# design.net
KiCad netlist of a schematic drawn in Altium Designer
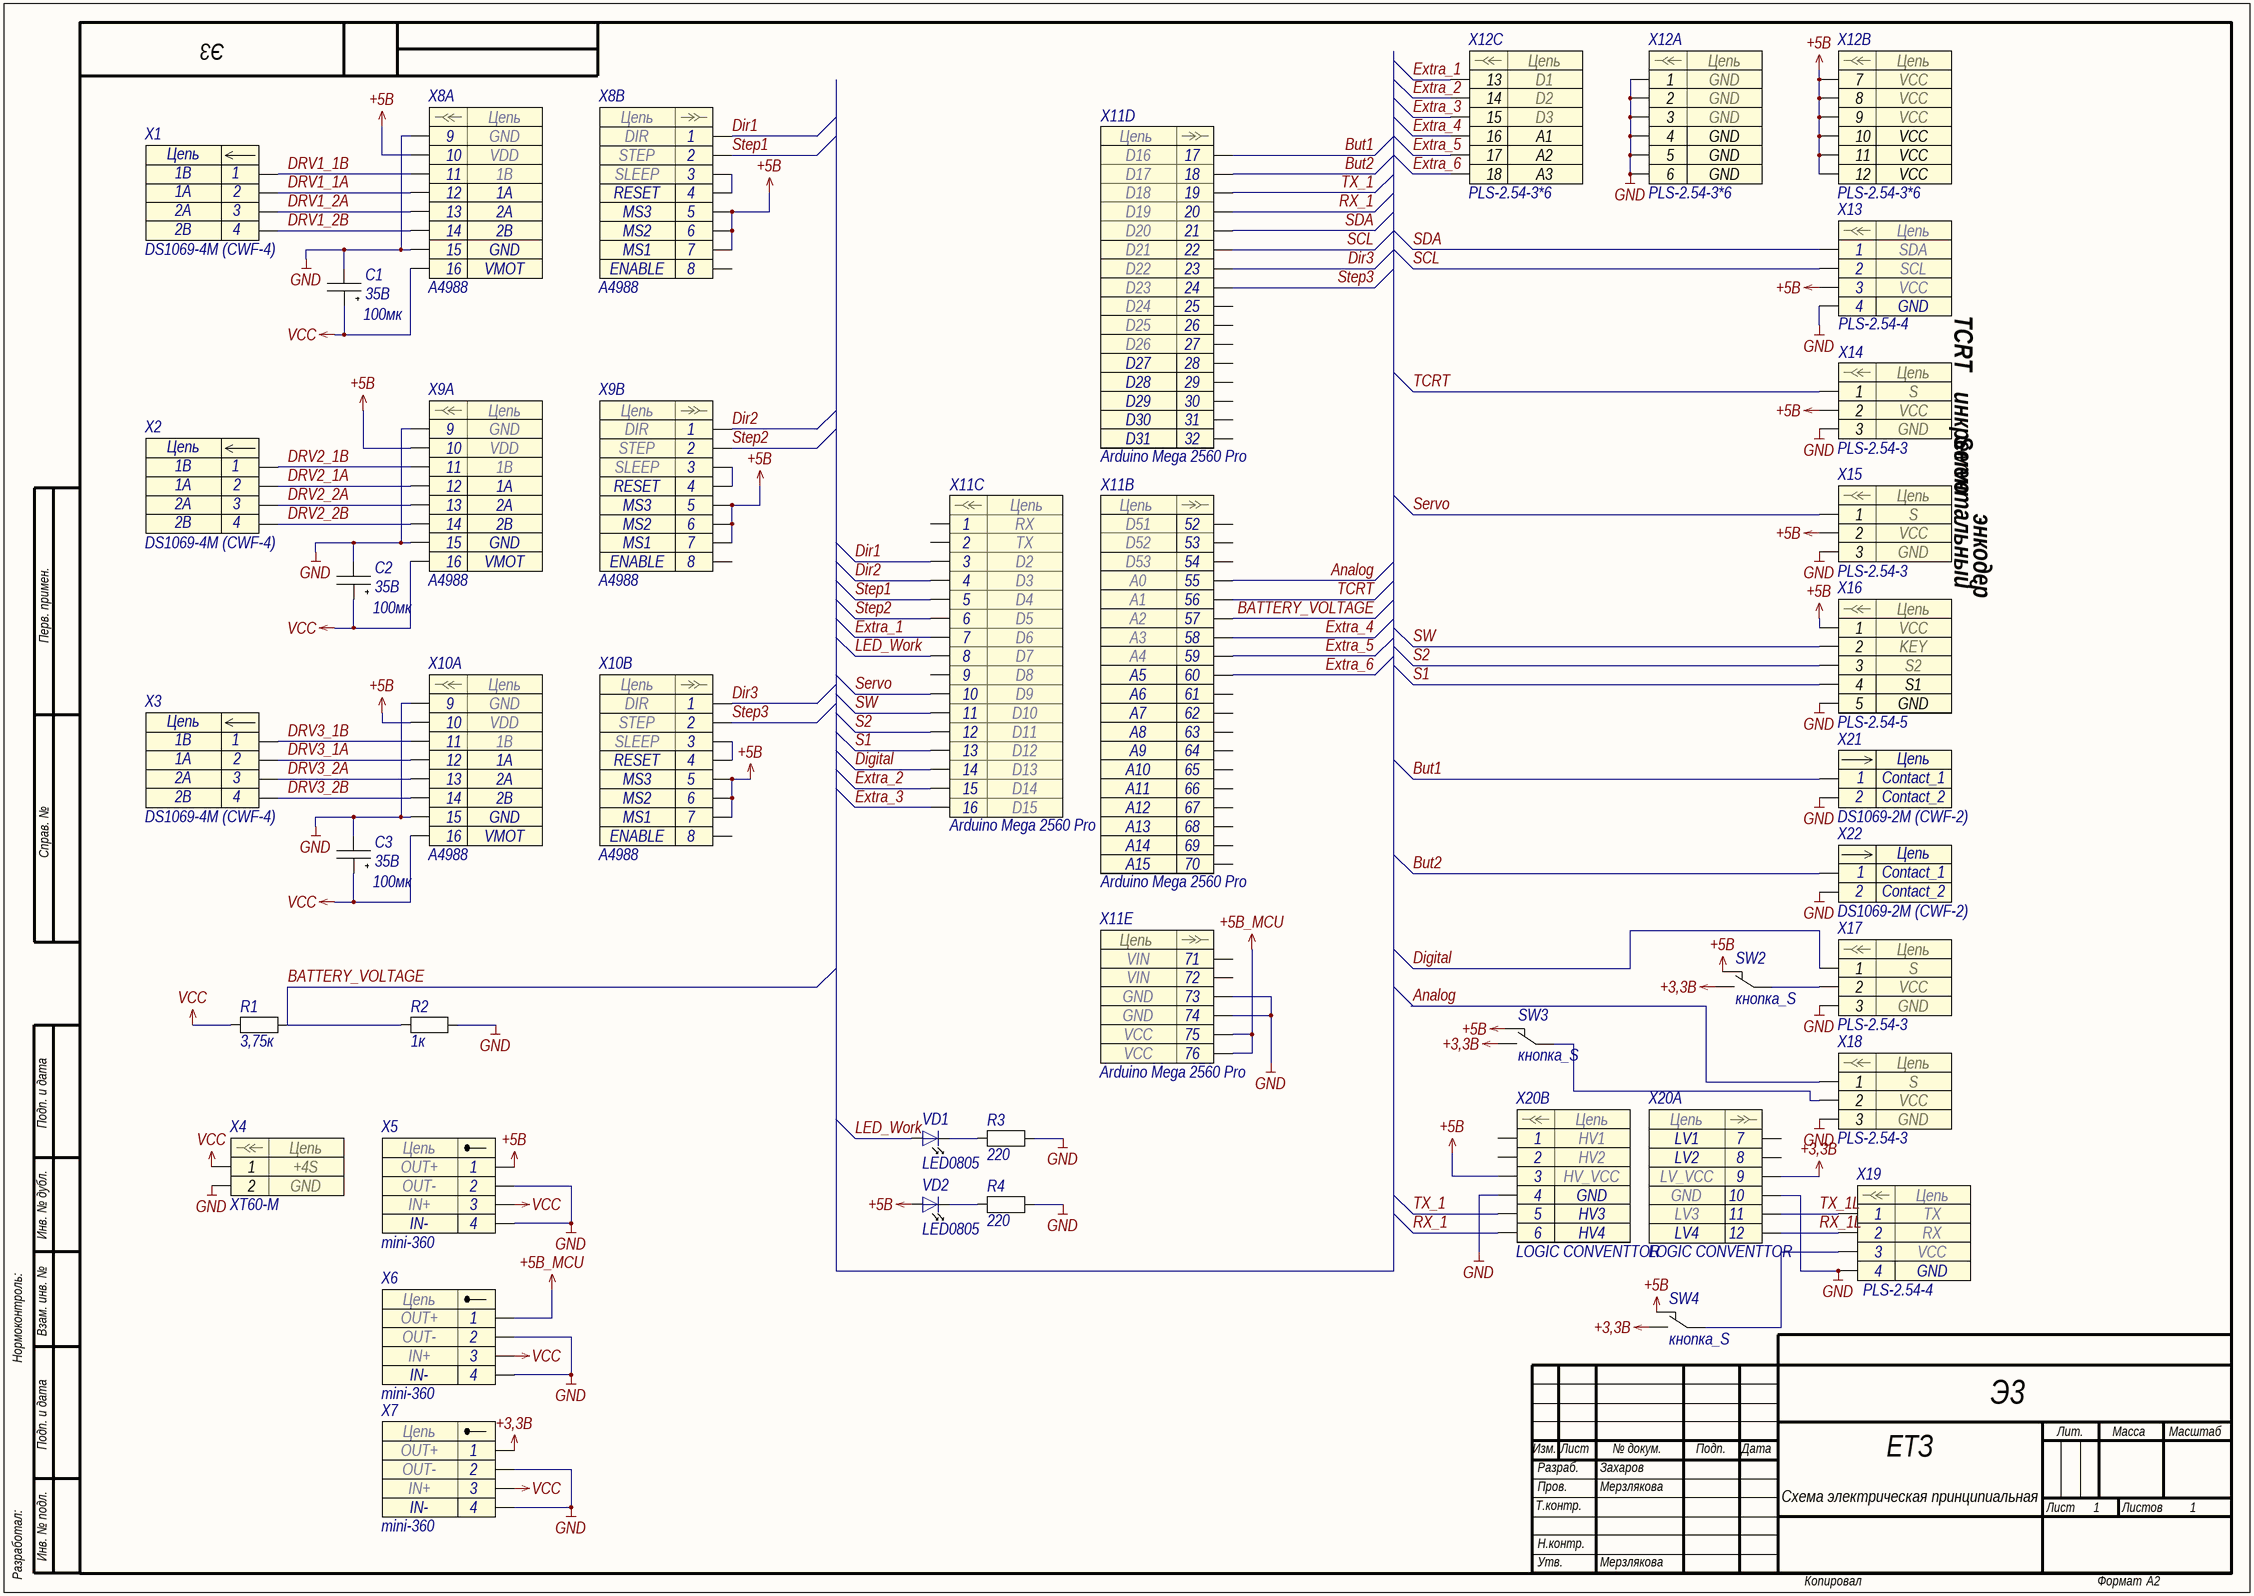
[diagram p0: Проект_ЕТЗ.SchDoc]

(export (version "E")
  (design (tool "Eeschema 10.0.6"))
  (components
    (comp (ref "C1")
      (value "am")
      (footprint "SK050M0100B3F-0811-up")
      (fields (field (name "VOLTAGE") "35В") (field (name "NOMINAL") "100мк"))
      (libsource (lib "LibraryPloshchadnaia") (part "CAPATION+470мк35В"))
    )
    (comp (ref "C2")
      (value "am")
      (footprint "SK050M0100B3F-0811-up")
      (fields (field (name "VOLTAGE") "35В") (field (name "NOMINAL") "100мк"))
      (libsource (lib "LibraryPloshchadnaia") (part "CAPATION+470мк35В"))
    )
    (comp (ref "C3")
      (value "am")
      (footprint "SK050M0100B3F-0811-up")
      (fields (field (name "VOLTAGE") "35В") (field (name "NOMINAL") "100мк"))
      (libsource (lib "LibraryPloshchadnaia") (part "CAPATION+470мк35В"))
    )
    (comp (ref "R1")
      (value "3,75к")
      (footprint "Resistor0805")
      (libsource (lib "LibraryPloshchadnaia") (part "RESISTOR"))
    )
    (comp (ref "R2")
      (value "1к")
      (footprint "Resistor0805")
      (libsource (lib "LibraryPloshchadnaia") (part "RESISTOR"))
    )
    (comp (ref "R3")
      (value "220")
      (footprint "Resistor0805")
      (libsource (lib "LibraryPloshchadnaia") (part "RESISTOR"))
    )
    (comp (ref "R4")
      (value "220")
      (footprint "Resistor0805")
      (libsource (lib "LibraryPloshchadnaia") (part "RESISTOR"))
    )
    (comp (ref "SW2")
      (value "кнопка_S")
      (footprint "SS-12D00G3")
      (description "крутые переключатели с бимов")
      (libsource (lib "LibraryPloshchadnaia") (part "BT992895"))
    )
    (comp (ref "SW3")
      (value "кнопка_S")
      (footprint "SS-12D00G3")
      (description "крутые переключатели с бимов")
      (libsource (lib "LibraryPloshchadnaia") (part "BT992895"))
    )
    (comp (ref "SW4")
      (value "кнопка_S")
      (footprint "SS-12D00G3")
      (description "крутые переключатели с бимов")
      (libsource (lib "LibraryPloshchadnaia") (part "BT992895"))
    )
    (comp (ref "VD1")
      (value "LED0805")
      (footprint "LED0805")
      (libsource (lib "LibraryPloshchadnaia") (part "LED0805"))
    )
    (comp (ref "VD2")
      (value "LED0805")
      (footprint "LED0805")
      (libsource (lib "LibraryPloshchadnaia") (part "LED0805"))
    )
    (comp (ref "X1")
      (value "DS1069-4M (CWF-4)")
      (footprint "CWF-4")
      (description "Разъем - 4 конт. прямая вилка на плату")
      (libsource (lib "headers") (part "CWF-4"))
    )
    (comp (ref "X2")
      (value "DS1069-4M (CWF-4)")
      (footprint "CWF-4")
      (description "Разъем - 4 конт. прямая вилка на плату")
      (libsource (lib "headers") (part "CWF-4"))
    )
    (comp (ref "X3")
      (value "DS1069-4M (CWF-4)")
      (footprint "CWF-4")
      (description "Разъем - 4 конт. прямая вилка на плату")
      (libsource (lib "headers") (part "CWF-4"))
    )
    (comp (ref "X4")
      (value "XT60-M")
      (footprint "AMASS_XT60-M")
      (description "Plug; DC supply; XT60; male; PIN: 2; for cable; soldered; 30A; 500V")
      (fields (field (name "MF") "AMASS"))
      (libsource (lib "XT60-M") (part "XT60-M"))
    )
    (comp (ref "X5")
      (value "mini-360")
      (footprint "mini360")
      (description "стаб 18 на 12 мм")
      (libsource (lib "LibraryPloshchadnaia") (part "mini360"))
    )
    (comp (ref "X6")
      (value "mini-360")
      (footprint "mini360")
      (description "стаб 18 на 12 мм")
      (libsource (lib "LibraryPloshchadnaia") (part "mini360"))
    )
    (comp (ref "X7")
      (value "mini-360")
      (footprint "mini360")
      (description "стаб 18 на 12 мм")
      (libsource (lib "LibraryPloshchadnaia") (part "mini360"))
    )
    (comp (ref "X8") (value "A4988") (footprint "A4988") (libsource (lib "") (part "A4988_1")))
    (comp (ref "X9") (value "A4988") (footprint "A4988") (libsource (lib "") (part "A4988_1")))
    (comp (ref "X10") (value "A4988") (footprint "A4988") (libsource (lib "") (part "A4988_1")))
    (comp (ref "X11")
      (value "Arduino Mega 2560 Pro")
      (footprint "PBD38")
      (libsource (lib "LibraryPloshchadnaia") (part "Arduino Mega 2560 Pro"))
    )
    (comp (ref "X12")
      (value "PLS-2.54-3*6")
      (footprint "PLS-2.54-3*6")
      (libsource (lib "LibraryPloshchadnaia") (part "PLS-2.54-3*6"))
    )
    (comp (ref "X13")
      (value "PLS-2.54-4")
      (footprint "oled 128x64 0.96inch")
      (fields (field (name "ALTIUM_UNNAMED_1") "PLS-2.54-4"))
      (libsource (lib "LibraryPloshchadnaia") (part "PLS-2.54-4"))
    )
    (comp (ref "X14")
      (value "PLS-2.54-3")
      (footprint "PLS-2.54-3")
      (libsource (lib "LibraryPloshchadnaia") (part "PLS-2.54-3"))
    )
    (comp (ref "X15")
      (value "PLS-2.54-3")
      (footprint "PLS-2.54-3")
      (libsource (lib "LibraryPloshchadnaia") (part "PLS-2.54-3"))
    )
    (comp (ref "X16")
      (value "PLS-2.54-5")
      (footprint "KY-040")
      (libsource (lib "LibraryPloshchadnaia") (part "Ky-040"))
    )
    (comp (ref "X17")
      (value "PLS-2.54-3")
      (footprint "PLS-2.54-3")
      (libsource (lib "LibraryPloshchadnaia") (part "PLS-2.54-3"))
    )
    (comp (ref "X18")
      (value "PLS-2.54-3")
      (footprint "PLS-2.54-3")
      (libsource (lib "LibraryPloshchadnaia") (part "PLS-2.54-3"))
    )
    (comp (ref "X19")
      (value "PLS-2.54-4")
      (footprint "PLS-2.54-4")
      (libsource (lib "LibraryPloshchadnaia") (part "PLS-2.54-4"))
    )
    (comp (ref "X20")
      (value "LOGIC CONVENTTOR")
      (footprint "LOGIC CONVENTOR")
      (libsource (lib "LibraryPloshchadnaia") (part "LOGIC CONVENTTOR"))
    )
    (comp (ref "X21")
      (value "DS1069-2M (CWF-2)")
      (footprint "CWF-2")
      (description "Разъем - 2 конт. прямая вилка на плату")
      (libsource (lib "headers") (part "CWF-2"))
    )
    (comp (ref "X22")
      (value "DS1069-2M (CWF-2)")
      (footprint "CWF-2")
      (description "Разъем - 2 конт. прямая вилка на плату")
      (libsource (lib "headers") (part "CWF-2"))
    )
  )
  (nets
    (net (code "1") (name "+3,3В") (class "Default")
      (node (ref "SW2") (pin "1") (pinfunction "1_1") (pintype "passive"))
      (node (ref "SW3") (pin "1") (pinfunction "1_1") (pintype "passive"))
      (node (ref "SW4") (pin "1") (pinfunction "1_1") (pintype "passive"))
      (node (ref "X20") (pin "9") (pinfunction "9_9") (pintype "passive"))
      (node (ref "X7") (pin "1") (pinfunction "1_1") (pintype "passive"))
    )
    (net (code "2") (name "+5В") (class "Default")
      (node (ref "SW2") (pin "3") (pinfunction "3_3") (pintype "passive"))
      (node (ref "SW3") (pin "3") (pinfunction "3_3") (pintype "passive"))
      (node (ref "SW4") (pin "3") (pinfunction "3_3") (pintype "passive"))
      (node (ref "VD2") (pin "2") (pinfunction "2_2") (pintype "passive"))
      (node (ref "X10") (pin "10") (pinfunction "10_10") (pintype "passive"))
      (node (ref "X10") (pin "5") (pinfunction "5_5") (pintype "passive"))
      (node (ref "X10") (pin "6") (pinfunction "6_6") (pintype "passive"))
      (node (ref "X10") (pin "7") (pinfunction "7_7") (pintype "passive"))
      (node (ref "X12") (pin "10") (pinfunction "10_10") (pintype "passive"))
      (node (ref "X12") (pin "11") (pinfunction "11_11") (pintype "passive"))
      (node (ref "X12") (pin "12") (pinfunction "12_12") (pintype "passive"))
      (node (ref "X12") (pin "7") (pinfunction "7_7") (pintype "passive"))
      (node (ref "X12") (pin "8") (pinfunction "8_8") (pintype "passive"))
      (node (ref "X12") (pin "9") (pinfunction "9_9") (pintype "passive"))
      (node (ref "X13") (pin "3") (pinfunction "3_3") (pintype "passive"))
      (node (ref "X14") (pin "2") (pinfunction "2_2") (pintype "passive"))
      (node (ref "X15") (pin "2") (pinfunction "2_2") (pintype "passive"))
      (node (ref "X16") (pin "1") (pinfunction "1_1") (pintype "passive"))
      (node (ref "X20") (pin "3") (pinfunction "3_3") (pintype "passive"))
      (node (ref "X5") (pin "1") (pinfunction "1_1") (pintype "passive"))
      (node (ref "X8") (pin "10") (pinfunction "10_10") (pintype "passive"))
      (node (ref "X8") (pin "5") (pinfunction "5_5") (pintype "passive"))
      (node (ref "X8") (pin "6") (pinfunction "6_6") (pintype "passive"))
      (node (ref "X8") (pin "7") (pinfunction "7_7") (pintype "passive"))
      (node (ref "X9") (pin "10") (pinfunction "10_10") (pintype "passive"))
      (node (ref "X9") (pin "5") (pinfunction "5_5") (pintype "passive"))
      (node (ref "X9") (pin "6") (pinfunction "6_6") (pintype "passive"))
      (node (ref "X9") (pin "7") (pinfunction "7_7") (pintype "passive"))
    )
    (net (code "3") (name "+5В_MCU") (class "Default")
      (node (ref "X11") (pin "75") (pinfunction "75_75") (pintype "passive"))
      (node (ref "X11") (pin "76") (pinfunction "76_76") (pintype "passive"))
      (node (ref "X6") (pin "1") (pinfunction "1_1") (pintype "passive"))
    )
    (net (code "4") (name "/Analog") (class "Default")
      (node (ref "X11") (pin "55") (pinfunction "55_55") (pintype "passive"))
      (node (ref "X18") (pin "1") (pinfunction "1_1") (pintype "passive"))
    )
    (net (code "5") (name "/BATTERY_VOLTAGE") (class "Default")
      (node (ref "R1") (pin "2") (pinfunction "2_2") (pintype "passive"))
      (node (ref "R2") (pin "1") (pinfunction "1_1") (pintype "passive"))
      (node (ref "X11") (pin "57") (pinfunction "57_57") (pintype "passive"))
    )
    (net (code "6") (name "/But1") (class "Default")
      (node (ref "X11") (pin "17") (pinfunction "17_17") (pintype "passive"))
      (node (ref "X21") (pin "1") (pinfunction "1_1") (pintype "passive"))
    )
    (net (code "7") (name "/But2") (class "Default")
      (node (ref "X11") (pin "18") (pinfunction "18_18") (pintype "passive"))
      (node (ref "X22") (pin "1") (pinfunction "1_1") (pintype "passive"))
    )
    (net (code "8") (name "/DRV1_1A") (class "Default")
      (node (ref "X1") (pin "2") (pinfunction "2_2") (pintype "passive"))
      (node (ref "X8") (pin "12") (pinfunction "12_12") (pintype "passive"))
    )
    (net (code "9") (name "/DRV1_1B") (class "Default")
      (node (ref "X1") (pin "1") (pinfunction "1_1") (pintype "passive"))
      (node (ref "X8") (pin "11") (pinfunction "11_11") (pintype "passive"))
    )
    (net (code "10") (name "/DRV1_2A") (class "Default")
      (node (ref "X1") (pin "3") (pinfunction "3_3") (pintype "passive"))
      (node (ref "X8") (pin "13") (pinfunction "13_13") (pintype "passive"))
    )
    (net (code "11") (name "/DRV1_2B") (class "Default")
      (node (ref "X1") (pin "4") (pinfunction "4_4") (pintype "passive"))
      (node (ref "X8") (pin "14") (pinfunction "14_14") (pintype "passive"))
    )
    (net (code "12") (name "/DRV2_1A") (class "Default")
      (node (ref "X2") (pin "2") (pinfunction "2_2") (pintype "passive"))
      (node (ref "X9") (pin "12") (pinfunction "12_12") (pintype "passive"))
    )
    (net (code "13") (name "/DRV2_1B") (class "Default")
      (node (ref "X2") (pin "1") (pinfunction "1_1") (pintype "passive"))
      (node (ref "X9") (pin "11") (pinfunction "11_11") (pintype "passive"))
    )
    (net (code "14") (name "/DRV2_2A") (class "Default")
      (node (ref "X2") (pin "3") (pinfunction "3_3") (pintype "passive"))
      (node (ref "X9") (pin "13") (pinfunction "13_13") (pintype "passive"))
    )
    (net (code "15") (name "/DRV2_2B") (class "Default")
      (node (ref "X2") (pin "4") (pinfunction "4_4") (pintype "passive"))
      (node (ref "X9") (pin "14") (pinfunction "14_14") (pintype "passive"))
    )
    (net (code "16") (name "/DRV3_1A") (class "Default")
      (node (ref "X10") (pin "12") (pinfunction "12_12") (pintype "passive"))
      (node (ref "X3") (pin "2") (pinfunction "2_2") (pintype "passive"))
    )
    (net (code "17") (name "/DRV3_1B") (class "Default")
      (node (ref "X10") (pin "11") (pinfunction "11_11") (pintype "passive"))
      (node (ref "X3") (pin "1") (pinfunction "1_1") (pintype "passive"))
    )
    (net (code "18") (name "/DRV3_2A") (class "Default")
      (node (ref "X10") (pin "13") (pinfunction "13_13") (pintype "passive"))
      (node (ref "X3") (pin "3") (pinfunction "3_3") (pintype "passive"))
    )
    (net (code "19") (name "/DRV3_2B") (class "Default")
      (node (ref "X10") (pin "14") (pinfunction "14_14") (pintype "passive"))
      (node (ref "X3") (pin "4") (pinfunction "4_4") (pintype "passive"))
    )
    (net (code "20") (name "/Digital") (class "Default")
      (node (ref "X11") (pin "14") (pinfunction "14_14") (pintype "passive"))
      (node (ref "X17") (pin "1") (pinfunction "1_1") (pintype "passive"))
    )
    (net (code "21") (name "/Dir1") (class "Default")
      (node (ref "X11") (pin "3") (pinfunction "3_3") (pintype "passive"))
      (node (ref "X8") (pin "1") (pinfunction "1_1") (pintype "passive"))
    )
    (net (code "22") (name "/Dir2") (class "Default")
      (node (ref "X11") (pin "4") (pinfunction "4_4") (pintype "passive"))
      (node (ref "X9") (pin "1") (pinfunction "1_1") (pintype "passive"))
    )
    (net (code "23") (name "/Dir3") (class "Default")
      (node (ref "X10") (pin "1") (pinfunction "1_1") (pintype "passive"))
      (node (ref "X11") (pin "23") (pinfunction "23_23") (pintype "passive"))
    )
    (net (code "24") (name "/Extra_1") (class "Default")
      (node (ref "X11") (pin "7") (pinfunction "7_7") (pintype "passive"))
      (node (ref "X12") (pin "13") (pinfunction "13_13") (pintype "passive"))
    )
    (net (code "25") (name "/Extra_2") (class "Default")
      (node (ref "X11") (pin "15") (pinfunction "15_15") (pintype "passive"))
      (node (ref "X12") (pin "14") (pinfunction "14_14") (pintype "passive"))
    )
    (net (code "26") (name "/Extra_3") (class "Default")
      (node (ref "X11") (pin "16") (pinfunction "16_16") (pintype "passive"))
      (node (ref "X12") (pin "15") (pinfunction "15_15") (pintype "passive"))
    )
    (net (code "27") (name "/Extra_4") (class "Default")
      (node (ref "X11") (pin "58") (pinfunction "58_58") (pintype "passive"))
      (node (ref "X12") (pin "16") (pinfunction "16_16") (pintype "passive"))
    )
    (net (code "28") (name "/Extra_5") (class "Default")
      (node (ref "X11") (pin "59") (pinfunction "59_59") (pintype "passive"))
      (node (ref "X12") (pin "17") (pinfunction "17_17") (pintype "passive"))
    )
    (net (code "29") (name "/Extra_6") (class "Default")
      (node (ref "X11") (pin "60") (pinfunction "60_60") (pintype "passive"))
      (node (ref "X12") (pin "18") (pinfunction "18_18") (pintype "passive"))
    )
    (net (code "30") (name "/LED_Work") (class "Default")
      (node (ref "VD1") (pin "2") (pinfunction "2_2") (pintype "passive"))
      (node (ref "X11") (pin "8") (pinfunction "8_8") (pintype "passive"))
    )
    (net (code "31") (name "/RX_1") (class "Default")
      (node (ref "X11") (pin "20") (pinfunction "20_20") (pintype "passive"))
      (node (ref "X20") (pin "6") (pinfunction "6_6") (pintype "passive"))
    )
    (net (code "32") (name "/RX_1L") (class "Default")
      (node (ref "X19") (pin "2") (pinfunction "2_2") (pintype "passive"))
      (node (ref "X20") (pin "12") (pinfunction "12_12") (pintype "passive"))
    )
    (net (code "33") (name "/S1") (class "Default")
      (node (ref "X11") (pin "13") (pinfunction "13_13") (pintype "passive"))
      (node (ref "X16") (pin "4") (pinfunction "4_4") (pintype "passive"))
    )
    (net (code "34") (name "/S2") (class "Default")
      (node (ref "X11") (pin "12") (pinfunction "12_12") (pintype "passive"))
      (node (ref "X16") (pin "3") (pinfunction "3_3") (pintype "passive"))
    )
    (net (code "35") (name "/SCL") (class "Default")
      (node (ref "X11") (pin "22") (pinfunction "22_22") (pintype "passive"))
      (node (ref "X13") (pin "2") (pinfunction "2_2") (pintype "passive"))
    )
    (net (code "36") (name "/SDA") (class "Default")
      (node (ref "X11") (pin "21") (pinfunction "21_21") (pintype "passive"))
      (node (ref "X13") (pin "1") (pinfunction "1_1") (pintype "passive"))
    )
    (net (code "37") (name "/SW") (class "Default")
      (node (ref "X11") (pin "11") (pinfunction "11_11") (pintype "passive"))
      (node (ref "X16") (pin "2") (pinfunction "2_2") (pintype "passive"))
    )
    (net (code "38") (name "/Servo") (class "Default")
      (node (ref "X11") (pin "10") (pinfunction "10_10") (pintype "passive"))
      (node (ref "X15") (pin "1") (pinfunction "1_1") (pintype "passive"))
    )
    (net (code "39") (name "/Step1") (class "Default")
      (node (ref "X11") (pin "5") (pinfunction "5_5") (pintype "passive"))
      (node (ref "X8") (pin "2") (pinfunction "2_2") (pintype "passive"))
    )
    (net (code "40") (name "/Step2") (class "Default")
      (node (ref "X11") (pin "6") (pinfunction "6_6") (pintype "passive"))
      (node (ref "X9") (pin "2") (pinfunction "2_2") (pintype "passive"))
    )
    (net (code "41") (name "/Step3") (class "Default")
      (node (ref "X10") (pin "2") (pinfunction "2_2") (pintype "passive"))
      (node (ref "X11") (pin "24") (pinfunction "24_24") (pintype "passive"))
    )
    (net (code "42") (name "/TCRT") (class "Default")
      (node (ref "X11") (pin "56") (pinfunction "56_56") (pintype "passive"))
      (node (ref "X14") (pin "1") (pinfunction "1_1") (pintype "passive"))
    )
    (net (code "43") (name "/TX_1") (class "Default")
      (node (ref "X11") (pin "19") (pinfunction "19_19") (pintype "passive"))
      (node (ref "X20") (pin "5") (pinfunction "5_5") (pintype "passive"))
    )
    (net (code "44") (name "/TX_1L") (class "Default")
      (node (ref "X19") (pin "1") (pinfunction "1_1") (pintype "passive"))
      (node (ref "X20") (pin "11") (pinfunction "11_11") (pintype "passive"))
    )
    (net (code "45") (name "GND") (class "Default")
      (node (ref "C1") (pin "1") (pinfunction "1_1") (pintype "passive"))
      (node (ref "C2") (pin "1") (pinfunction "1_1") (pintype "passive"))
      (node (ref "C3") (pin "1") (pinfunction "1_1") (pintype "passive"))
      (node (ref "R2") (pin "2") (pinfunction "2_2") (pintype "passive"))
      (node (ref "R3") (pin "2") (pinfunction "2_2") (pintype "passive"))
      (node (ref "R4") (pin "2") (pinfunction "2_2") (pintype "passive"))
      (node (ref "X10") (pin "15") (pinfunction "15_15") (pintype "passive"))
      (node (ref "X10") (pin "9") (pinfunction "9_9") (pintype "passive"))
      (node (ref "X11") (pin "73") (pinfunction "73_73") (pintype "passive"))
      (node (ref "X11") (pin "74") (pinfunction "74_74") (pintype "passive"))
      (node (ref "X12") (pin "1") (pinfunction "1_1") (pintype "passive"))
      (node (ref "X12") (pin "2") (pinfunction "2_2") (pintype "passive"))
      (node (ref "X12") (pin "3") (pinfunction "3_3") (pintype "passive"))
      (node (ref "X12") (pin "4") (pinfunction "4_4") (pintype "passive"))
      (node (ref "X12") (pin "5") (pinfunction "5_5") (pintype "passive"))
      (node (ref "X12") (pin "6") (pinfunction "6_6") (pintype "passive"))
      (node (ref "X13") (pin "4") (pinfunction "4_4") (pintype "passive"))
      (node (ref "X14") (pin "3") (pinfunction "3_3") (pintype "passive"))
      (node (ref "X15") (pin "3") (pinfunction "3_3") (pintype "passive"))
      (node (ref "X16") (pin "5") (pinfunction "5_5") (pintype "passive"))
      (node (ref "X17") (pin "3") (pinfunction "3_3") (pintype "passive"))
      (node (ref "X18") (pin "3") (pinfunction "3_3") (pintype "passive"))
      (node (ref "X19") (pin "4") (pinfunction "4_4") (pintype "passive"))
      (node (ref "X20") (pin "10") (pinfunction "10_10") (pintype "passive"))
      (node (ref "X20") (pin "4") (pinfunction "4_4") (pintype "passive"))
      (node (ref "X21") (pin "2") (pinfunction "2_2") (pintype "passive"))
      (node (ref "X22") (pin "2") (pinfunction "2_2") (pintype "passive"))
      (node (ref "X4") (pin "2") (pinfunction "2_2") (pintype "passive"))
      (node (ref "X5") (pin "2") (pinfunction "2_2") (pintype "passive"))
      (node (ref "X5") (pin "4") (pinfunction "4_4") (pintype "passive"))
      (node (ref "X6") (pin "2") (pinfunction "2_2") (pintype "passive"))
      (node (ref "X6") (pin "4") (pinfunction "4_4") (pintype "passive"))
      (node (ref "X7") (pin "2") (pinfunction "2_2") (pintype "passive"))
      (node (ref "X7") (pin "4") (pinfunction "4_4") (pintype "passive"))
      (node (ref "X8") (pin "15") (pinfunction "15_15") (pintype "passive"))
      (node (ref "X8") (pin "9") (pinfunction "9_9") (pintype "passive"))
      (node (ref "X9") (pin "15") (pinfunction "15_15") (pintype "passive"))
      (node (ref "X9") (pin "9") (pinfunction "9_9") (pintype "passive"))
    )
    (net (code "46") (name "Net-(R3-Pad1)") (class "Default")
      (node (ref "R3") (pin "1") (pinfunction "1_1") (pintype "passive"))
      (node (ref "VD1") (pin "1") (pinfunction "1_1") (pintype "passive"))
    )
    (net (code "47") (name "Net-(R4-Pad1)") (class "Default")
      (node (ref "R4") (pin "1") (pinfunction "1_1") (pintype "passive"))
      (node (ref "VD2") (pin "1") (pinfunction "1_1") (pintype "passive"))
    )
    (net (code "48") (name "Net-(SW2-Pad2)") (class "Default")
      (node (ref "SW2") (pin "2") (pinfunction "2_2") (pintype "passive"))
      (node (ref "X17") (pin "2") (pinfunction "2_2") (pintype "passive"))
    )
    (net (code "49") (name "Net-(SW3-Pad2)") (class "Default")
      (node (ref "SW3") (pin "2") (pinfunction "2_2") (pintype "passive"))
      (node (ref "X18") (pin "2") (pinfunction "2_2") (pintype "passive"))
    )
    (net (code "50") (name "Net-(SW4-Pad2)") (class "Default")
      (node (ref "SW4") (pin "2") (pinfunction "2_2") (pintype "passive"))
      (node (ref "X19") (pin "3") (pinfunction "3_3") (pintype "passive"))
    )
    (net (code "51") (name "Net-(X8-Pad3)") (class "Default")
      (node (ref "X8") (pin "3") (pinfunction "3_3") (pintype "passive"))
      (node (ref "X8") (pin "4") (pinfunction "4_4") (pintype "passive"))
    )
    (net (code "52") (name "Net-(X9-Pad3)") (class "Default")
      (node (ref "X9") (pin "3") (pinfunction "3_3") (pintype "passive"))
      (node (ref "X9") (pin "4") (pinfunction "4_4") (pintype "passive"))
    )
    (net (code "53") (name "Net-(X10-Pad3)") (class "Default")
      (node (ref "X10") (pin "3") (pinfunction "3_3") (pintype "passive"))
      (node (ref "X10") (pin "4") (pinfunction "4_4") (pintype "passive"))
    )
    (net (code "54") (name "VCC") (class "Default")
      (node (ref "C1") (pin "2") (pinfunction "2_2") (pintype "passive"))
      (node (ref "C2") (pin "2") (pinfunction "2_2") (pintype "passive"))
      (node (ref "C3") (pin "2") (pinfunction "2_2") (pintype "passive"))
      (node (ref "R1") (pin "1") (pinfunction "1_1") (pintype "passive"))
      (node (ref "X10") (pin "16") (pinfunction "16_16") (pintype "passive"))
      (node (ref "X4") (pin "1") (pinfunction "1_1") (pintype "passive"))
      (node (ref "X5") (pin "3") (pinfunction "3_3") (pintype "passive"))
      (node (ref "X6") (pin "3") (pinfunction "3_3") (pintype "passive"))
      (node (ref "X7") (pin "3") (pinfunction "3_3") (pintype "passive"))
      (node (ref "X8") (pin "16") (pinfunction "16_16") (pintype "passive"))
      (node (ref "X9") (pin "16") (pinfunction "16_16") (pintype "passive"))
    )
    (net (code "55") (name "unconnected-(X5-Pad1)") (class "Default")
      (node (ref "X5") (pin "1") (pinfunction "1_1") (pintype "passive"))
    )
    (net (code "56") (name "unconnected-(X6-Pad1)") (class "Default")
      (node (ref "X6") (pin "1") (pinfunction "1_1") (pintype "passive"))
    )
    (net (code "57") (name "unconnected-(X7-Pad1)") (class "Default")
      (node (ref "X7") (pin "1") (pinfunction "1_1") (pintype "passive"))
    )
    (net (code "58") (name "unconnected-(X8-Pad8)") (class "Default")
      (node (ref "X8") (pin "8") (pinfunction "8_8") (pintype "passive"))
    )
    (net (code "59") (name "unconnected-(X9-Pad8)") (class "Default")
      (node (ref "X9") (pin "8") (pinfunction "8_8") (pintype "passive"))
    )
    (net (code "60") (name "unconnected-(X10-Pad8)") (class "Default")
      (node (ref "X10") (pin "8") (pinfunction "8_8") (pintype "passive"))
    )
    (net (code "61") (name "unconnected-(X11-Pad1)") (class "Default")
      (node (ref "X11") (pin "1") (pinfunction "1_1") (pintype "passive"))
    )
    (net (code "62") (name "unconnected-(X11-Pad2)") (class "Default")
      (node (ref "X11") (pin "2") (pinfunction "2_2") (pintype "passive"))
    )
    (net (code "63") (name "unconnected-(X11-Pad9)") (class "Default")
      (node (ref "X11") (pin "9") (pinfunction "9_9") (pintype "passive"))
    )
    (net (code "64") (name "unconnected-(X11-Pad25)") (class "Default")
      (node (ref "X11") (pin "25") (pinfunction "25_25") (pintype "passive"))
    )
    (net (code "65") (name "unconnected-(X11-Pad26)") (class "Default")
      (node (ref "X11") (pin "26") (pinfunction "26_26") (pintype "passive"))
    )
    (net (code "66") (name "unconnected-(X11-Pad27)") (class "Default")
      (node (ref "X11") (pin "27") (pinfunction "27_27") (pintype "passive"))
    )
    (net (code "67") (name "unconnected-(X11-Pad28)") (class "Default")
      (node (ref "X11") (pin "28") (pinfunction "28_28") (pintype "passive"))
    )
    (net (code "68") (name "unconnected-(X11-Pad29)") (class "Default")
      (node (ref "X11") (pin "29") (pinfunction "29_29") (pintype "passive"))
    )
    (net (code "69") (name "unconnected-(X11-Pad30)") (class "Default")
      (node (ref "X11") (pin "30") (pinfunction "30_30") (pintype "passive"))
    )
    (net (code "70") (name "unconnected-(X11-Pad31)") (class "Default")
      (node (ref "X11") (pin "31") (pinfunction "31_31") (pintype "passive"))
    )
    (net (code "71") (name "unconnected-(X11-Pad32)") (class "Default")
      (node (ref "X11") (pin "32") (pinfunction "32_32") (pintype "passive"))
    )
    (net (code "72") (name "unconnected-(X11-Pad52)") (class "Default")
      (node (ref "X11") (pin "52") (pinfunction "52_52") (pintype "passive"))
    )
    (net (code "73") (name "unconnected-(X11-Pad53)") (class "Default")
      (node (ref "X11") (pin "53") (pinfunction "53_53") (pintype "passive"))
    )
    (net (code "74") (name "unconnected-(X11-Pad54)") (class "Default")
      (node (ref "X11") (pin "54") (pinfunction "54_54") (pintype "passive"))
    )
    (net (code "75") (name "unconnected-(X11-Pad61)") (class "Default")
      (node (ref "X11") (pin "61") (pinfunction "61_61") (pintype "passive"))
    )
    (net (code "76") (name "unconnected-(X11-Pad62)") (class "Default")
      (node (ref "X11") (pin "62") (pinfunction "62_62") (pintype "passive"))
    )
    (net (code "77") (name "unconnected-(X11-Pad63)") (class "Default")
      (node (ref "X11") (pin "63") (pinfunction "63_63") (pintype "passive"))
    )
    (net (code "78") (name "unconnected-(X11-Pad64)") (class "Default")
      (node (ref "X11") (pin "64") (pinfunction "64_64") (pintype "passive"))
    )
    (net (code "79") (name "unconnected-(X11-Pad65)") (class "Default")
      (node (ref "X11") (pin "65") (pinfunction "65_65") (pintype "passive"))
    )
    (net (code "80") (name "unconnected-(X11-Pad66)") (class "Default")
      (node (ref "X11") (pin "66") (pinfunction "66_66") (pintype "passive"))
    )
    (net (code "81") (name "unconnected-(X11-Pad67)") (class "Default")
      (node (ref "X11") (pin "67") (pinfunction "67_67") (pintype "passive"))
    )
    (net (code "82") (name "unconnected-(X11-Pad68)") (class "Default")
      (node (ref "X11") (pin "68") (pinfunction "68_68") (pintype "passive"))
    )
    (net (code "83") (name "unconnected-(X11-Pad69)") (class "Default")
      (node (ref "X11") (pin "69") (pinfunction "69_69") (pintype "passive"))
    )
    (net (code "84") (name "unconnected-(X11-Pad70)") (class "Default")
      (node (ref "X11") (pin "70") (pinfunction "70_70") (pintype "passive"))
    )
    (net (code "85") (name "unconnected-(X11-Pad71)") (class "Default")
      (node (ref "X11") (pin "71") (pinfunction "71_71") (pintype "passive"))
    )
    (net (code "86") (name "unconnected-(X11-Pad72)") (class "Default")
      (node (ref "X11") (pin "72") (pinfunction "72_72") (pintype "passive"))
    )
    (net (code "87") (name "unconnected-(X20-Pad1)") (class "Default")
      (node (ref "X20") (pin "1") (pinfunction "1_1") (pintype "passive"))
    )
    (net (code "88") (name "unconnected-(X20-Pad2)") (class "Default")
      (node (ref "X20") (pin "2") (pinfunction "2_2") (pintype "passive"))
    )
    (net (code "89") (name "unconnected-(X20-Pad7)") (class "Default")
      (node (ref "X20") (pin "7") (pinfunction "7_7") (pintype "passive"))
    )
    (net (code "90") (name "unconnected-(X20-Pad8)") (class "Default")
      (node (ref "X20") (pin "8") (pinfunction "8_8") (pintype "passive"))
    )
  )
)
